# spi_lcd_v3.net
KiCad netlist of a schematic drawn in EAGLE
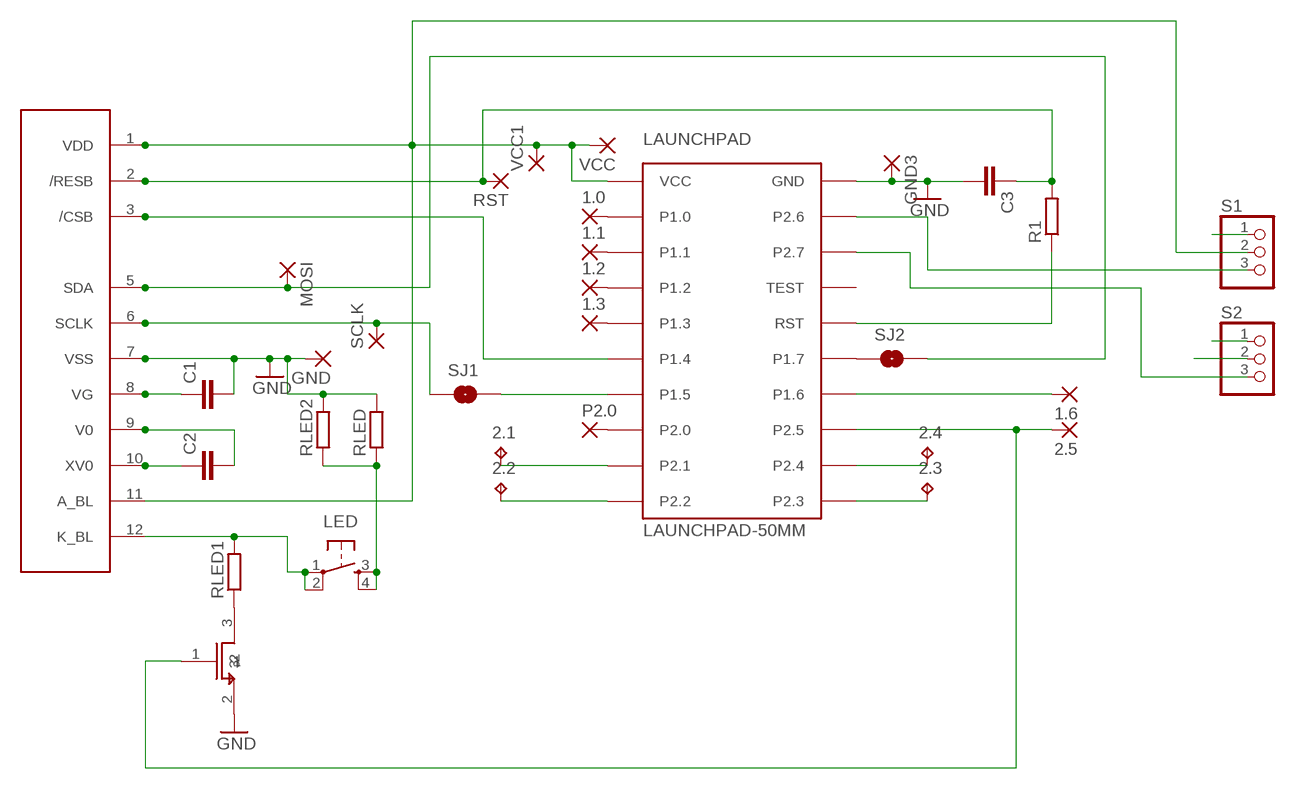
[diagram p0: schematic, sheet 1]

(export (version "E")
  (design (tool "Eeschema 10.0.6"))
  (components
    (comp (ref "1.0")
      (value "2,15/1,0")
      (footprint "eagle-import:2,15_1,0")
      (libsource (lib "eagle-import") (part "2,15/1,0"))
    )
    (comp (ref "1.1")
      (value "2,15/1,0")
      (footprint "eagle-import:2,15_1,0")
      (libsource (lib "eagle-import") (part "2,15/1,0"))
    )
    (comp (ref "1.2")
      (value "2,15/1,0")
      (footprint "eagle-import:2,15_1,0")
      (libsource (lib "eagle-import") (part "2,15/1,0"))
    )
    (comp (ref "1.3")
      (value "2,15/1,0")
      (footprint "eagle-import:2,15_1,0")
      (libsource (lib "eagle-import") (part "2,15/1,0"))
    )
    (comp (ref "1.6")
      (value "2,15/1,0")
      (footprint "eagle-import:2,15_1,0")
      (libsource (lib "eagle-import") (part "2,15/1,0"))
    )
    (comp (ref "2.1")
      (value "TPTP07R")
      (footprint "eagle-import:TP07R")
      (libsource (lib "eagle-import") (part "TPTP07R"))
    )
    (comp (ref "2.2")
      (value "TPTP07R")
      (footprint "eagle-import:TP07R")
      (libsource (lib "eagle-import") (part "TPTP07R"))
    )
    (comp (ref "2.3")
      (value "TPTP07R")
      (footprint "eagle-import:TP07R")
      (libsource (lib "eagle-import") (part "TPTP07R"))
    )
    (comp (ref "2.4")
      (value "TPTP07R")
      (footprint "eagle-import:TP07R")
      (libsource (lib "eagle-import") (part "TPTP07R"))
    )
    (comp (ref "2.5")
      (value "2,15/1,0")
      (footprint "eagle-import:2,15_1,0")
      (libsource (lib "eagle-import") (part "2,15/1,0"))
    )
    (comp (ref "C1")
      (value "CAP1206")
      (footprint "eagle-import:1206")
      (libsource (lib "eagle-import") (part "CAP1206"))
    )
    (comp (ref "C2")
      (value "CAP1206")
      (footprint "eagle-import:1206")
      (libsource (lib "eagle-import") (part "CAP1206"))
    )
    (comp (ref "C3")
      (value "CAP1206")
      (footprint "eagle-import:1206")
      (libsource (lib "eagle-import") (part "CAP1206"))
    )
    (comp (ref "GND")
      (value "2,15/1,0")
      (footprint "eagle-import:2,15_1,0")
      (libsource (lib "eagle-import") (part "2,15/1,0"))
    )
    (comp (ref "GND3")
      (value "2,15/1,0")
      (footprint "eagle-import:2,15_1,0")
      (libsource (lib "eagle-import") (part "2,15/1,0"))
    )
    (comp (ref "LAUNCHPAD")
      (value "LAUNCHPAD-50MM")
      (footprint "eagle-import:LAUNCHPAD-50MM")
      (libsource (lib "eagle-import") (part "LAUNCHPAD-50MM"))
    )
    (comp (ref "LED")
      (value "TAC_SWITCHPTH")
      (footprint "eagle-import:TACTILE-PTH")
      (libsource (lib "eagle-import") (part "TAC_SWITCHPTH"))
    )
    (comp (ref "LEDSW")
      (value "2N7002PW")
      (footprint "eagle-import:SOT323-R")
      (libsource (lib "eagle-import") (part "2N7002PW"))
    )
    (comp (ref "MOSI")
      (value "2,15/1,0")
      (footprint "eagle-import:2,15_1,0")
      (libsource (lib "eagle-import") (part "2,15/1,0"))
    )
    (comp (ref "P2.0")
      (value "2,15/1,0")
      (footprint "eagle-import:2,15_1,0")
      (libsource (lib "eagle-import") (part "2,15/1,0"))
    )
    (comp (ref "R1")
      (value "R-EU_R1206")
      (footprint "eagle-import:R1206")
      (libsource (lib "eagle-import") (part "R-EU_R1206"))
    )
    (comp (ref "RLED")
      (value "R-EU_R1206")
      (footprint "eagle-import:R1206")
      (libsource (lib "eagle-import") (part "R-EU_R1206"))
    )
    (comp (ref "RLED1")
      (value "R-EU_R1206")
      (footprint "eagle-import:R1206")
      (libsource (lib "eagle-import") (part "R-EU_R1206"))
    )
    (comp (ref "RLED2")
      (value "R-EU_0207/7")
      (footprint "eagle-import:0207_7")
      (libsource (lib "eagle-import") (part "R-EU_0207/7"))
    )
    (comp (ref "RST")
      (value "2,15/1,0")
      (footprint "eagle-import:2,15_1,0")
      (libsource (lib "eagle-import") (part "2,15/1,0"))
    )
    (comp (ref "S1")
      (value "PINHD-1X3")
      (footprint "eagle-import:1X03")
      (libsource (lib "eagle-import") (part "PINHD-1X3"))
    )
    (comp (ref "S2")
      (value "PINHD-1X3")
      (footprint "eagle-import:1X03")
      (libsource (lib "eagle-import") (part "PINHD-1X3"))
    )
    (comp (ref "SCLK")
      (value "2,15/1,0")
      (footprint "eagle-import:2,15_1,0")
      (libsource (lib "eagle-import") (part "2,15/1,0"))
    )
    (comp (ref "SJ1")
      (value "SOLDERJUMPERTRACE")
      (footprint "eagle-import:SJ_2S-TRACE")
      (libsource (lib "eagle-import") (part "SOLDERJUMPERTRACE"))
    )
    (comp (ref "SJ2")
      (value "SOLDERJUMPERTRACE")
      (footprint "eagle-import:SJ_2S-TRACE")
      (libsource (lib "eagle-import") (part "SOLDERJUMPERTRACE"))
    )
    (comp (ref "U$1")
      (value "PE9665WRFPE9665WRF-WHOLE")
      (footprint "eagle-import:PE9665WRF")
      (libsource (lib "eagle-import") (part "PE9665WRFPE9665WRF-WHOLE"))
    )
    (comp (ref "VCC")
      (value "2,15/1,0")
      (footprint "eagle-import:2,15_1,0")
      (libsource (lib "eagle-import") (part "2,15/1,0"))
    )
    (comp (ref "VCC1")
      (value "2,15/1,0")
      (footprint "eagle-import:2,15_1,0")
      (libsource (lib "eagle-import") (part "2,15/1,0"))
    )
  )
  (nets
    (net (code "1") (name "/VCC") (class "Default")
      (node (ref "LAUNCHPAD") (pin "VCC") (pinfunction "VCC_VCC") (pintype "power_in"))
      (node (ref "S1") (pin "2") (pinfunction "2_2") (pintype "passive"))
      (node (ref "S2") (pin "2") (pinfunction "2_2") (pintype "passive"))
      (node (ref "U$1") (pin "1") (pinfunction "VDD_1") (pintype "bidirectional"))
      (node (ref "U$1") (pin "11") (pinfunction "A_BL_11") (pintype "bidirectional"))
      (node (ref "VCC") (pin "1") (pinfunction "P_1") (pintype "passive"))
      (node (ref "VCC1") (pin "1") (pinfunction "P_1") (pintype "passive"))
    )
    (net (code "2") (name "GND") (class "Default")
      (node (ref "C1") (pin "2") (pinfunction "2_2") (pintype "passive"))
      (node (ref "C3") (pin "2") (pinfunction "2_2") (pintype "passive"))
      (node (ref "GND") (pin "1") (pinfunction "P_1") (pintype "passive"))
      (node (ref "GND3") (pin "1") (pinfunction "P_1") (pintype "passive"))
      (node (ref "LAUNCHPAD") (pin "GND") (pinfunction "GND_GND") (pintype "power_in"))
      (node (ref "LEDSW") (pin "2") (pinfunction "2_2") (pintype "bidirectional"))
      (node (ref "RLED") (pin "2") (pinfunction "2_2") (pintype "passive"))
      (node (ref "RLED2") (pin "2") (pinfunction "2_2") (pintype "passive"))
      (node (ref "S1") (pin "1") (pinfunction "1_1") (pintype "passive"))
      (node (ref "S2") (pin "1") (pinfunction "1_1") (pintype "passive"))
      (node (ref "U$1") (pin "7") (pinfunction "VSS_7") (pintype "bidirectional"))
    )
    (net (code "3") (name "Net-(1.0-P)") (class "Default")
      (node (ref "1.0") (pin "1") (pinfunction "P_1") (pintype "passive"))
      (node (ref "LAUNCHPAD") (pin "P1.0") (pinfunction "P1.0_P1.0") (pintype "bidirectional"))
    )
    (net (code "4") (name "Net-(1.1-P)") (class "Default")
      (node (ref "1.1") (pin "1") (pinfunction "P_1") (pintype "passive"))
      (node (ref "LAUNCHPAD") (pin "P1.1") (pinfunction "P1.1_P1.1") (pintype "bidirectional"))
    )
    (net (code "5") (name "Net-(1.2-P)") (class "Default")
      (node (ref "1.2") (pin "1") (pinfunction "P_1") (pintype "passive"))
      (node (ref "LAUNCHPAD") (pin "P1.2") (pinfunction "P1.2_P1.2") (pintype "bidirectional"))
    )
    (net (code "6") (name "Net-(1.3-P)") (class "Default")
      (node (ref "1.3") (pin "1") (pinfunction "P_1") (pintype "passive"))
      (node (ref "LAUNCHPAD") (pin "P1.3") (pinfunction "P1.3_P1.3") (pintype "bidirectional"))
    )
    (net (code "7") (name "Net-(1.6-P)") (class "Default")
      (node (ref "1.6") (pin "1") (pinfunction "P_1") (pintype "passive"))
      (node (ref "LAUNCHPAD") (pin "P1.6") (pinfunction "P1.6_P1.6") (pintype "bidirectional"))
    )
    (net (code "8") (name "Net-(2.1-PadTP)") (class "Default")
      (node (ref "2.1") (pin "TP") (pinfunction "TP_TP") (pintype "input"))
      (node (ref "LAUNCHPAD") (pin "P2.1") (pinfunction "P2.1_P2.1") (pintype "bidirectional"))
    )
    (net (code "9") (name "Net-(2.2-PadTP)") (class "Default")
      (node (ref "2.2") (pin "TP") (pinfunction "TP_TP") (pintype "input"))
      (node (ref "LAUNCHPAD") (pin "P2.2") (pinfunction "P2.2_P2.2") (pintype "bidirectional"))
    )
    (net (code "10") (name "Net-(2.3-PadTP)") (class "Default")
      (node (ref "2.3") (pin "TP") (pinfunction "TP_TP") (pintype "input"))
      (node (ref "LAUNCHPAD") (pin "P2.3") (pinfunction "P2.3_P2.3") (pintype "bidirectional"))
    )
    (net (code "11") (name "Net-(2.4-PadTP)") (class "Default")
      (node (ref "2.4") (pin "TP") (pinfunction "TP_TP") (pintype "input"))
      (node (ref "LAUNCHPAD") (pin "P2.4") (pinfunction "P2.4_P2.4") (pintype "bidirectional"))
    )
    (net (code "12") (name "Net-(2.5-P)") (class "Default")
      (node (ref "2.5") (pin "1") (pinfunction "P_1") (pintype "passive"))
      (node (ref "LAUNCHPAD") (pin "P2.5") (pinfunction "P2.5_P2.5") (pintype "bidirectional"))
      (node (ref "LEDSW") (pin "1") (pinfunction "1_1") (pintype "bidirectional"))
    )
    (net (code "13") (name "Net-(LAUNCHPAD-PadP1.5)") (class "Default")
      (node (ref "LAUNCHPAD") (pin "P1.5") (pinfunction "P1.5_P1.5") (pintype "bidirectional"))
      (node (ref "SJ1") (pin "2") (pinfunction "2_2") (pintype "passive"))
    )
    (net (code "14") (name "Net-(LAUNCHPAD-PadP1.7)") (class "Default")
      (node (ref "LAUNCHPAD") (pin "P1.7") (pinfunction "P1.7_P1.7") (pintype "bidirectional"))
      (node (ref "SJ2") (pin "1") (pinfunction "1_1") (pintype "passive"))
    )
    (net (code "15") (name "Net-(LAUNCHPAD-PadP2.6)") (class "Default")
      (node (ref "LAUNCHPAD") (pin "P2.6") (pinfunction "P2.6_P2.6") (pintype "bidirectional"))
      (node (ref "S1") (pin "3") (pinfunction "3_3") (pintype "passive"))
    )
    (net (code "16") (name "Net-(LAUNCHPAD-PadP2.7)") (class "Default")
      (node (ref "LAUNCHPAD") (pin "P2.7") (pinfunction "P2.7_P2.7") (pintype "bidirectional"))
      (node (ref "S2") (pin "3") (pinfunction "3_3") (pintype "passive"))
    )
    (net (code "17") (name "Net-(LAUNCHPAD-PadRST)") (class "Default")
      (node (ref "LAUNCHPAD") (pin "RST") (pinfunction "RST_RST") (pintype "bidirectional"))
      (node (ref "R1") (pin "1") (pinfunction "1_1") (pintype "passive"))
    )
    (net (code "18") (name "Net-(LED-Pad3)") (class "Default")
      (node (ref "LED") (pin "3") (pinfunction "3_3") (pintype "passive"))
      (node (ref "LED") (pin "4") (pinfunction "4_4") (pintype "passive"))
      (node (ref "RLED") (pin "1") (pinfunction "1_1") (pintype "passive"))
      (node (ref "RLED2") (pin "1") (pinfunction "1_1") (pintype "passive"))
    )
    (net (code "19") (name "Net-(LEDSW-Pad3)") (class "Default")
      (node (ref "LEDSW") (pin "3") (pinfunction "3_3") (pintype "bidirectional"))
      (node (ref "RLED1") (pin "1") (pinfunction "1_1") (pintype "passive"))
    )
    (net (code "20") (name "Net-(MOSI-P)") (class "Default")
      (node (ref "MOSI") (pin "1") (pinfunction "P_1") (pintype "passive"))
      (node (ref "SJ2") (pin "2") (pinfunction "2_2") (pintype "passive"))
      (node (ref "U$1") (pin "5") (pinfunction "SDA_5") (pintype "bidirectional"))
    )
    (net (code "21") (name "Net-(P2.0-P)") (class "Default")
      (node (ref "LAUNCHPAD") (pin "P2.0") (pinfunction "P2.0_P2.0") (pintype "bidirectional"))
      (node (ref "P2.0") (pin "1") (pinfunction "P_1") (pintype "passive"))
    )
    (net (code "22") (name "Net-(RST-P)") (class "Default")
      (node (ref "C3") (pin "1") (pinfunction "1_1") (pintype "passive"))
      (node (ref "R1") (pin "2") (pinfunction "2_2") (pintype "passive"))
      (node (ref "RST") (pin "1") (pinfunction "P_1") (pintype "passive"))
      (node (ref "U$1") (pin "2") (pinfunction "/RESB_2") (pintype "bidirectional"))
    )
    (net (code "23") (name "Net-(SCLK-P)") (class "Default")
      (node (ref "SCLK") (pin "1") (pinfunction "P_1") (pintype "passive"))
      (node (ref "SJ1") (pin "1") (pinfunction "1_1") (pintype "passive"))
      (node (ref "U$1") (pin "6") (pinfunction "SCLK_6") (pintype "bidirectional"))
    )
    (net (code "24") (name "Net-(U$1-K_BL)") (class "Default")
      (node (ref "LED") (pin "1") (pinfunction "1_1") (pintype "passive"))
      (node (ref "LED") (pin "2") (pinfunction "2_2") (pintype "passive"))
      (node (ref "RLED1") (pin "2") (pinfunction "2_2") (pintype "passive"))
      (node (ref "U$1") (pin "12") (pinfunction "K_BL_12") (pintype "bidirectional"))
    )
    (net (code "25") (name "Net-(U$1-V0)") (class "Default")
      (node (ref "C2") (pin "2") (pinfunction "2_2") (pintype "passive"))
      (node (ref "U$1") (pin "9") (pinfunction "V0_9") (pintype "bidirectional"))
    )
    (net (code "26") (name "Net-(U$1-VG)") (class "Default")
      (node (ref "C1") (pin "1") (pinfunction "1_1") (pintype "passive"))
      (node (ref "U$1") (pin "8") (pinfunction "VG_8") (pintype "bidirectional"))
    )
    (net (code "27") (name "Net-(U$1-XV0)") (class "Default")
      (node (ref "C2") (pin "1") (pinfunction "1_1") (pintype "passive"))
      (node (ref "U$1") (pin "10") (pinfunction "XV0_10") (pintype "bidirectional"))
    )
    (net (code "28") (name "Net-(U$1-{slash}CSB)") (class "Default")
      (node (ref "LAUNCHPAD") (pin "P1.4") (pinfunction "P1.4_P1.4") (pintype "bidirectional"))
      (node (ref "U$1") (pin "3") (pinfunction "/CSB_3") (pintype "bidirectional"))
    )
    (net (code "29") (name "unconnected-(LAUNCHPAD-PadTEST)") (class "Default")
      (node (ref "LAUNCHPAD") (pin "TEST") (pinfunction "TEST_TEST") (pintype "bidirectional"))
    )
  )
)
